# early-bird.net
KiCad netlist of a schematic drawn in EAGLE
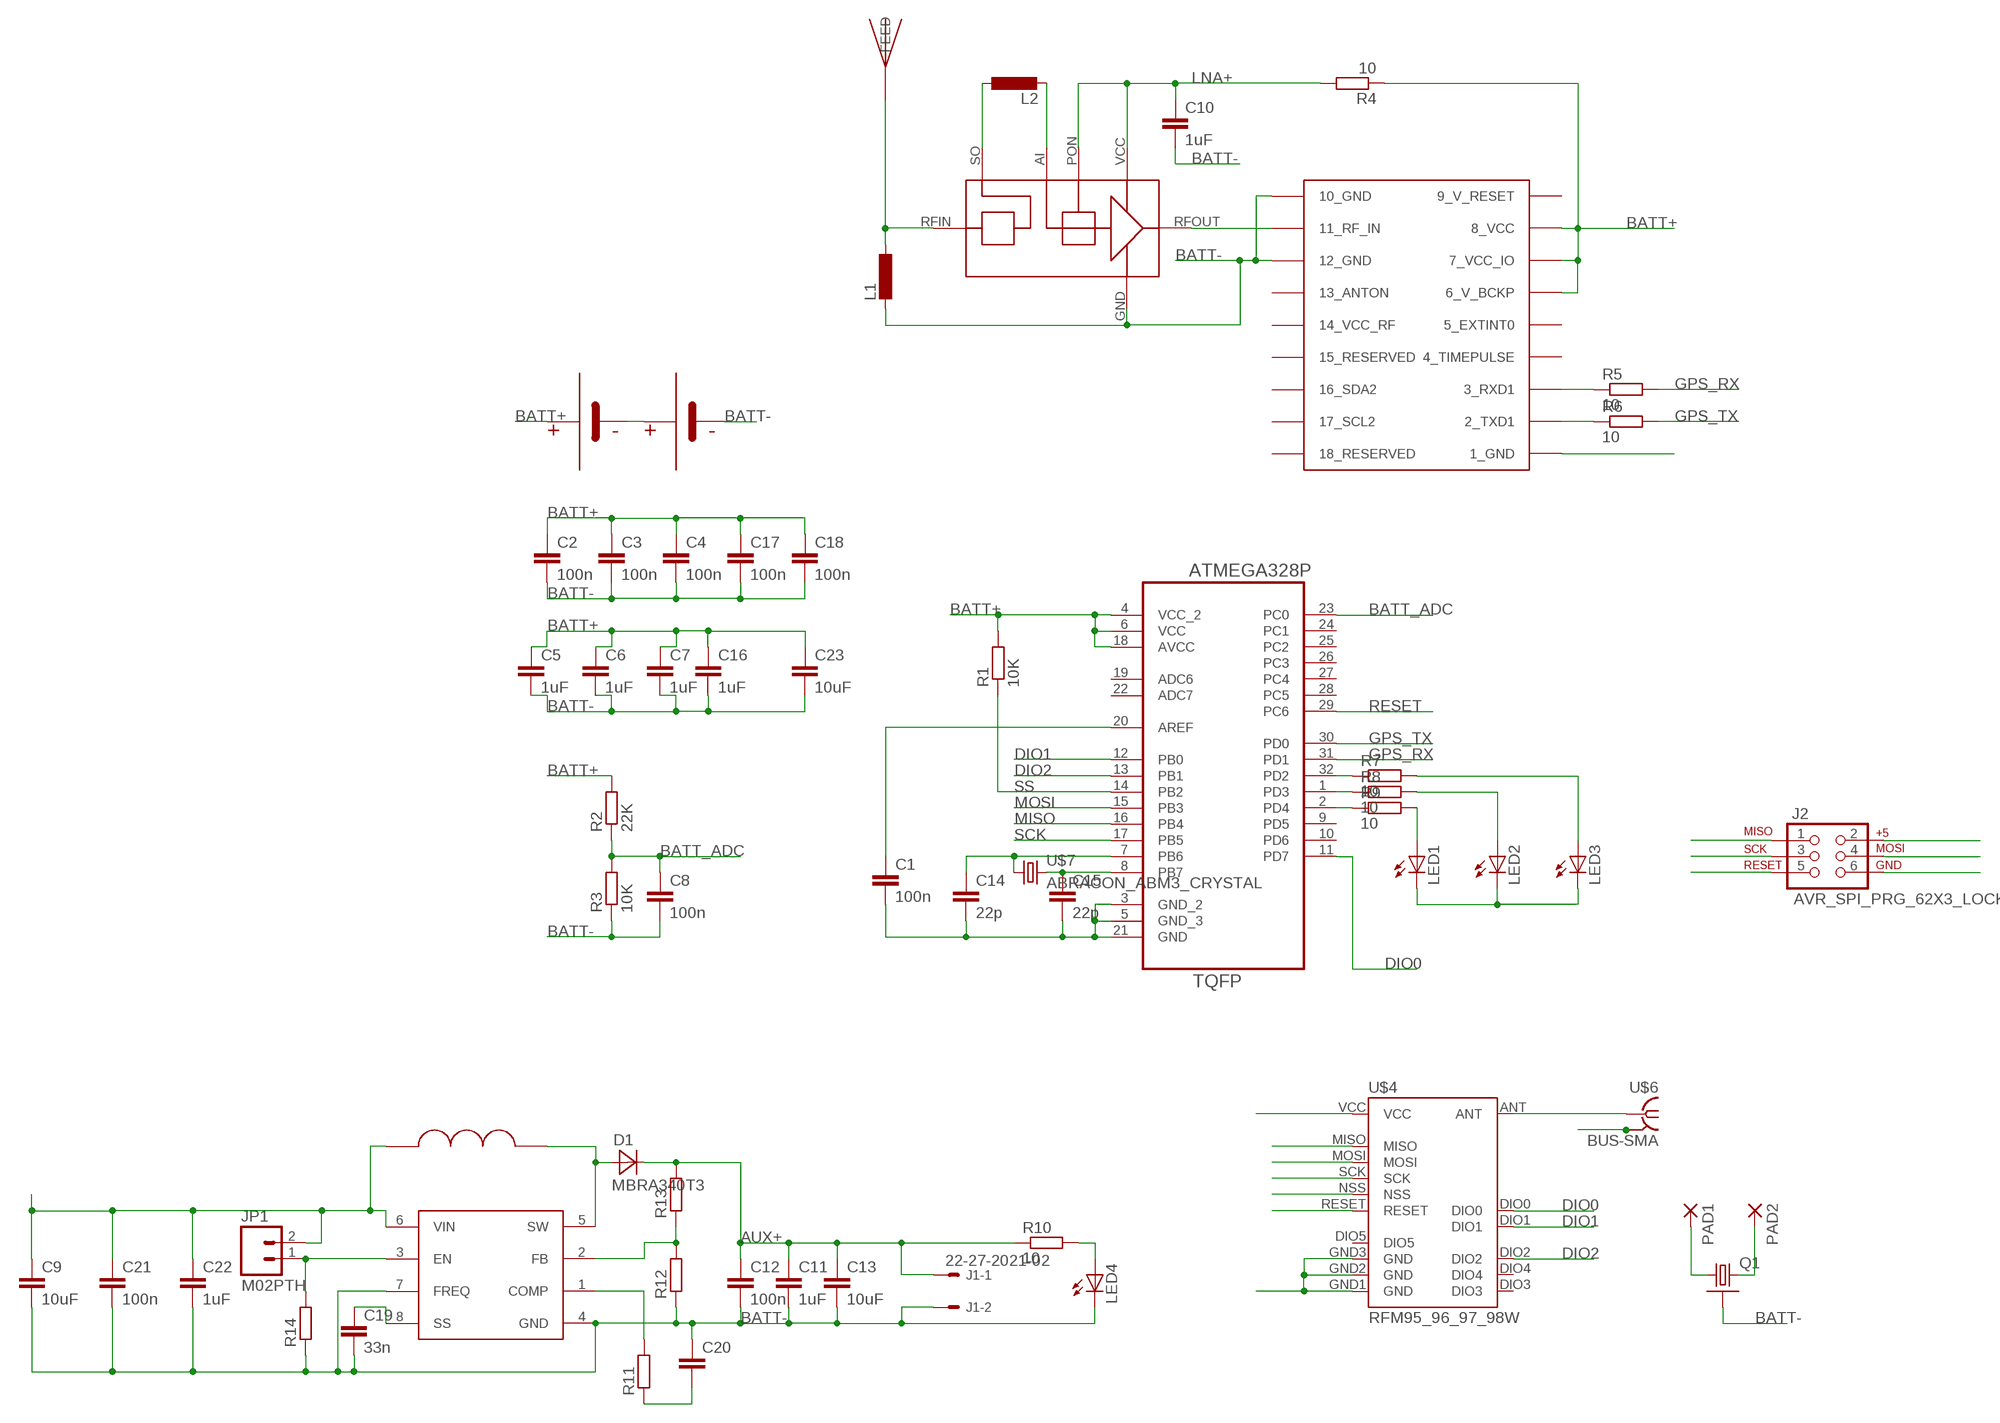
[diagram p0: schematic, sheet 1]

(export (version "E")
  (design (tool "Eeschema 10.0.6"))
  (components
    (comp (ref "C1")
      (value "100n")
      (footprint "eagle-import:C0402")
      (libsource (lib "eagle-import") (part "C-EUC0402"))
    )
    (comp (ref "C2")
      (value "100n")
      (footprint "eagle-import:C0402")
      (libsource (lib "eagle-import") (part "C-EUC0402"))
    )
    (comp (ref "C3")
      (value "100n")
      (footprint "eagle-import:C0402")
      (libsource (lib "eagle-import") (part "C-EUC0402"))
    )
    (comp (ref "C4")
      (value "100n")
      (footprint "eagle-import:C0402")
      (libsource (lib "eagle-import") (part "C-EUC0402"))
    )
    (comp (ref "C5")
      (value "1uF")
      (footprint "eagle-import:C0603")
      (libsource (lib "eagle-import") (part "C-EUC0603"))
    )
    (comp (ref "C6")
      (value "1uF")
      (footprint "eagle-import:C0603")
      (libsource (lib "eagle-import") (part "C-EUC0603"))
    )
    (comp (ref "C7")
      (value "1uF")
      (footprint "eagle-import:C0603")
      (libsource (lib "eagle-import") (part "C-EUC0603"))
    )
    (comp (ref "C8")
      (value "100n")
      (footprint "eagle-import:C0402")
      (libsource (lib "eagle-import") (part "C-EUC0402"))
    )
    (comp (ref "C9")
      (value "10uF")
      (footprint "eagle-import:C1210")
      (libsource (lib "eagle-import") (part "C-EUC1210"))
    )
    (comp (ref "C10")
      (value "1uF")
      (footprint "eagle-import:C0603")
      (libsource (lib "eagle-import") (part "C-EUC0603"))
    )
    (comp (ref "C11")
      (value "1uF")
      (footprint "eagle-import:C0603")
      (libsource (lib "eagle-import") (part "C-EUC0603"))
    )
    (comp (ref "C12")
      (value "100n")
      (footprint "eagle-import:C0402")
      (libsource (lib "eagle-import") (part "C-EUC0402"))
    )
    (comp (ref "C13")
      (value "10uF")
      (footprint "eagle-import:C1210")
      (libsource (lib "eagle-import") (part "C-EUC1210"))
    )
    (comp (ref "C14")
      (value "22p")
      (footprint "eagle-import:C0402")
      (libsource (lib "eagle-import") (part "C-EUC0402"))
    )
    (comp (ref "C15")
      (value "22p")
      (footprint "eagle-import:C0402")
      (libsource (lib "eagle-import") (part "C-EUC0402"))
    )
    (comp (ref "C16")
      (value "1uF")
      (footprint "eagle-import:C0603")
      (libsource (lib "eagle-import") (part "C-EUC0603"))
    )
    (comp (ref "C17")
      (value "100n")
      (footprint "eagle-import:C0402")
      (libsource (lib "eagle-import") (part "C-EUC0402"))
    )
    (comp (ref "C18")
      (value "100n")
      (footprint "eagle-import:C0402")
      (libsource (lib "eagle-import") (part "C-EUC0402"))
    )
    (comp (ref "C19")
      (value "33n")
      (footprint "eagle-import:C0402")
      (libsource (lib "eagle-import") (part "C-EUC0402"))
    )
    (comp (ref "C20")
      (value "C-EUC0402")
      (footprint "eagle-import:C0402")
      (libsource (lib "eagle-import") (part "C-EUC0402"))
    )
    (comp (ref "C21")
      (value "100n")
      (footprint "eagle-import:C0402")
      (libsource (lib "eagle-import") (part "C-EUC0402"))
    )
    (comp (ref "C22")
      (value "1uF")
      (footprint "eagle-import:C0603")
      (libsource (lib "eagle-import") (part "C-EUC0603"))
    )
    (comp (ref "C23")
      (value "10uF")
      (footprint "eagle-import:C1210")
      (libsource (lib "eagle-import") (part "C-EUC1210"))
    )
    (comp (ref "D1")
      (value "MBRA340T3")
      (footprint "eagle-import:SMA")
      (libsource (lib "eagle-import") (part "MBRA340T3"))
    )
    (comp (ref "J1")
      (value "22-27-2021-02")
      (footprint "eagle-import:6410-02")
      (libsource (lib "eagle-import") (part "22-?-0227-2021"))
    )
    (comp (ref "J2")
      (value "AVR_SPI_PRG_62X3_LOCK")
      (footprint "eagle-import:2X3_LOCK")
      (libsource (lib "eagle-import") (part "AVR_SPI_PRG_62X3_LOCK"))
    )
    (comp (ref "JP1")
      (value "M02PTH")
      (footprint "eagle-import:1X02")
      (libsource (lib "eagle-import") (part "M02PTH"))
    )
    (comp (ref "L1")
      (value "L-EUL2012C")
      (footprint "eagle-import:L2012C")
      (libsource (lib "eagle-import") (part "L-EUL2012C"))
    )
    (comp (ref "L2")
      (value "L-EUL2012C")
      (footprint "eagle-import:L2012C")
      (libsource (lib "eagle-import") (part "L-EUL2012C"))
    )
    (comp (ref "LED1")
      (value "LEDCHIPLED_1206")
      (footprint "eagle-import:CHIPLED_1206")
      (libsource (lib "eagle-import") (part "LEDCHIPLED_1206"))
    )
    (comp (ref "LED2")
      (value "LEDCHIPLED_1206")
      (footprint "eagle-import:CHIPLED_1206")
      (libsource (lib "eagle-import") (part "LEDCHIPLED_1206"))
    )
    (comp (ref "LED3")
      (value "LEDCHIPLED_1206")
      (footprint "eagle-import:CHIPLED_1206")
      (libsource (lib "eagle-import") (part "LEDCHIPLED_1206"))
    )
    (comp (ref "LED4")
      (value "LEDCHIPLED_1206")
      (footprint "eagle-import:CHIPLED_1206")
      (libsource (lib "eagle-import") (part "LEDCHIPLED_1206"))
    )
    (comp (ref "PAD1")
      (value "SMD2")
      (footprint "eagle-import:SMD1,27-2,54")
      (libsource (lib "eagle-import") (part "SMD2"))
    )
    (comp (ref "PAD2")
      (value "SMD2")
      (footprint "eagle-import:SMD1,27-2,54")
      (libsource (lib "eagle-import") (part "SMD2"))
    )
    (comp (ref "Q1")
      (value "CRYSTALCTS406")
      (footprint "eagle-import:CTS406")
      (libsource (lib "eagle-import") (part "CRYSTALCTS406"))
    )
    (comp (ref "R1")
      (value "10K")
      (footprint "eagle-import:R0402")
      (libsource (lib "eagle-import") (part "R-EU_R0402"))
    )
    (comp (ref "R2")
      (value "22K")
      (footprint "eagle-import:R0402")
      (libsource (lib "eagle-import") (part "R-EU_R0402"))
    )
    (comp (ref "R3")
      (value "10K")
      (footprint "eagle-import:R0402")
      (libsource (lib "eagle-import") (part "R-EU_R0402"))
    )
    (comp (ref "R4")
      (value "10")
      (footprint "eagle-import:R0402")
      (libsource (lib "eagle-import") (part "R-EU_R0402"))
    )
    (comp (ref "R5")
      (value "10")
      (footprint "eagle-import:R0402")
      (libsource (lib "eagle-import") (part "R-EU_R0402"))
    )
    (comp (ref "R6")
      (value "10")
      (footprint "eagle-import:R0402")
      (libsource (lib "eagle-import") (part "R-EU_R0402"))
    )
    (comp (ref "R7")
      (value "10")
      (footprint "eagle-import:R0402")
      (libsource (lib "eagle-import") (part "R-EU_R0402"))
    )
    (comp (ref "R8")
      (value "10")
      (footprint "eagle-import:R0402")
      (libsource (lib "eagle-import") (part "R-EU_R0402"))
    )
    (comp (ref "R9")
      (value "10")
      (footprint "eagle-import:R0402")
      (libsource (lib "eagle-import") (part "R-EU_R0402"))
    )
    (comp (ref "R10")
      (value "10")
      (footprint "eagle-import:R0402")
      (libsource (lib "eagle-import") (part "R-EU_R0402"))
    )
    (comp (ref "R11")
      (value "R-EU_R0402")
      (footprint "eagle-import:R0402")
      (libsource (lib "eagle-import") (part "R-EU_R0402"))
    )
    (comp (ref "R12")
      (value "R-EU_R0402")
      (footprint "eagle-import:R0402")
      (libsource (lib "eagle-import") (part "R-EU_R0402"))
    )
    (comp (ref "R13")
      (value "R-EU_R0402")
      (footprint "eagle-import:R0402")
      (libsource (lib "eagle-import") (part "R-EU_R0402"))
    )
    (comp (ref "R14")
      (value "R-EU_R0402")
      (footprint "eagle-import:R0402")
      (libsource (lib "eagle-import") (part "R-EU_R0402"))
    )
    (comp (ref "U$1")
      (value "KEYSTONE-92-AA-BATTERY-HOLDER")
      (footprint "eagle-import:KEYSTONE-92-AA-BATTERY")
      (libsource (lib "eagle-import") (part "KEYSTONE-92-AA-BATTERY-HOLDER"))
    )
    (comp (ref "U$2")
      (value "KEYSTONE-92-AA-BATTERY-HOLDER")
      (footprint "eagle-import:KEYSTONE-92-AA-BATTERY")
      (libsource (lib "eagle-import") (part "KEYSTONE-92-AA-BATTERY-HOLDER"))
    )
    (comp (ref "U$3")
      (value "JTI_ANTENNA-1575AT43A40")
      (footprint "eagle-import:JTI_ANTENNA-1575AT43A40")
      (libsource (lib "eagle-import") (part "JTI_ANTENNA-1575AT43A40"))
    )
    (comp (ref "U$4")
      (value "RFM95_96_97_98W")
      (footprint "eagle-import:RFM95_96_97_98W")
      (libsource (lib "eagle-import") (part "RFM95_96_97_98W"))
    )
    (comp (ref "U$5")
      (value "UBLOX_MAX")
      (footprint "eagle-import:UBLOX_MAX")
      (libsource (lib "eagle-import") (part "UBLOX_MAX"))
    )
    (comp (ref "U$6")
      (value "BUS-SMA")
      (footprint "eagle-import:BUS-SMA")
      (libsource (lib "eagle-import") (part "BUS-SMA"))
    )
    (comp (ref "U$7")
      (value "ABRACON_ABM3_CRYSTAL")
      (footprint "eagle-import:ABRACON_ABM3_CRYSTAL")
      (libsource (lib "eagle-import") (part "ABRACON_ABM3_CRYSTAL"))
    )
    (comp (ref "U$8")
      (value "ADP1612")
      (footprint "eagle-import:SOP65P490X110-8N")
      (libsource (lib "eagle-import") (part "ADP1612"))
    )
    (comp (ref "U$9")
      (value "BGM1034N7")
      (footprint "eagle-import:TSNP-7-10")
      (libsource (lib "eagle-import") (part "BGM1034N7"))
    )
    (comp (ref "U$10")
      (value "MULTICOMP_8MM_INDUCTOR")
      (footprint "eagle-import:8MM_SQ_INDUCTOR")
      (libsource (lib "eagle-import") (part "MULTICOMP_8MM_INDUCTOR"))
    )
    (comp (ref "U1")
      (value "ATMEGA328P-AU")
      (footprint "eagle-import:QFP80P900X900X120-32N")
      (libsource (lib "eagle-import") (part "ATMEGA328P-AU"))
    )
  )
  (nets
    (net (code "1") (name "/9_V_RESET") (class "Default")
      (node (ref "U$5") (pin "9_V_RESET") (pinfunction "9_V_RESET_9_V_RESET") (pintype "power_in"))
    )
    (net (code "2") (name "/AUX+") (class "Default")
      (node (ref "C11") (pin "1") (pinfunction "1_1") (pintype "passive"))
      (node (ref "C12") (pin "1") (pinfunction "1_1") (pintype "passive"))
      (node (ref "C13") (pin "1") (pinfunction "1_1") (pintype "passive"))
      (node (ref "D1") (pin "C") (pinfunction "C_C") (pintype "passive"))
      (node (ref "J1") (pin "1") (pinfunction "S_1") (pintype "passive"))
      (node (ref "R10") (pin "1") (pinfunction "1_1") (pintype "passive"))
      (node (ref "R13") (pin "2") (pinfunction "2_2") (pintype "passive"))
    )
    (net (code "3") (name "/BATT+") (class "Default")
      (node (ref "C16") (pin "1") (pinfunction "1_1") (pintype "passive"))
      (node (ref "C17") (pin "1") (pinfunction "1_1") (pintype "passive"))
      (node (ref "C18") (pin "1") (pinfunction "1_1") (pintype "passive"))
      (node (ref "C2") (pin "1") (pinfunction "1_1") (pintype "passive"))
      (node (ref "C21") (pin "1") (pinfunction "1_1") (pintype "passive"))
      (node (ref "C22") (pin "1") (pinfunction "1_1") (pintype "passive"))
      (node (ref "C23") (pin "1") (pinfunction "1_1") (pintype "passive"))
      (node (ref "C3") (pin "1") (pinfunction "1_1") (pintype "passive"))
      (node (ref "C4") (pin "1") (pinfunction "1_1") (pintype "passive"))
      (node (ref "C5") (pin "1") (pinfunction "1_1") (pintype "passive"))
      (node (ref "C6") (pin "1") (pinfunction "1_1") (pintype "passive"))
      (node (ref "C7") (pin "1") (pinfunction "1_1") (pintype "passive"))
      (node (ref "C9") (pin "1") (pinfunction "1_1") (pintype "passive"))
      (node (ref "J2") (pin "2") (pinfunction "2_2") (pintype "passive"))
      (node (ref "JP1") (pin "2") (pinfunction "2_2") (pintype "passive"))
      (node (ref "R1") (pin "2") (pinfunction "2_2") (pintype "passive"))
      (node (ref "R2") (pin "2") (pinfunction "2_2") (pintype "passive"))
      (node (ref "R4") (pin "1") (pinfunction "1_1") (pintype "passive"))
      (node (ref "U$1") (pin "VBATT") (pinfunction "BATT+_VBATT") (pintype "bidirectional"))
      (node (ref "U$1") (pin "VBATT1") (pinfunction "BATT+_VBATT1") (pintype "bidirectional"))
      (node (ref "U$10") (pin "P$2") (pinfunction "P$2_P$2") (pintype "bidirectional"))
      (node (ref "U$4") (pin "VCC") (pinfunction "VCC_VCC") (pintype "bidirectional"))
      (node (ref "U$5") (pin "6_V_BCKP") (pinfunction "6_V_BCKP_6_V_BCKP") (pintype "bidirectional"))
      (node (ref "U$5") (pin "7_VCC_IO") (pinfunction "7_VCC_IO_7_VCC_IO") (pintype "power_in"))
      (node (ref "U$5") (pin "8_VCC") (pinfunction "8_VCC_8_VCC") (pintype "power_in"))
      (node (ref "U$8") (pin "6") (pinfunction "VIN_6") (pintype "bidirectional"))
      (node (ref "U1") (pin "18") (pinfunction "AVCC_18") (pintype "power_in"))
      (node (ref "U1") (pin "4") (pinfunction "VCC_2_4") (pintype "power_in"))
      (node (ref "U1") (pin "6") (pinfunction "VCC_6") (pintype "power_in"))
    )
    (net (code "4") (name "/BATT-") (class "Default")
      (node (ref "C1") (pin "2") (pinfunction "2_2") (pintype "passive"))
      (node (ref "C10") (pin "2") (pinfunction "2_2") (pintype "passive"))
      (node (ref "C11") (pin "2") (pinfunction "2_2") (pintype "passive"))
      (node (ref "C12") (pin "2") (pinfunction "2_2") (pintype "passive"))
      (node (ref "C13") (pin "2") (pinfunction "2_2") (pintype "passive"))
      (node (ref "C14") (pin "2") (pinfunction "2_2") (pintype "passive"))
      (node (ref "C15") (pin "2") (pinfunction "2_2") (pintype "passive"))
      (node (ref "C16") (pin "2") (pinfunction "2_2") (pintype "passive"))
      (node (ref "C17") (pin "2") (pinfunction "2_2") (pintype "passive"))
      (node (ref "C18") (pin "2") (pinfunction "2_2") (pintype "passive"))
      (node (ref "C19") (pin "2") (pinfunction "2_2") (pintype "passive"))
      (node (ref "C2") (pin "2") (pinfunction "2_2") (pintype "passive"))
      (node (ref "C20") (pin "1") (pinfunction "1_1") (pintype "passive"))
      (node (ref "C21") (pin "2") (pinfunction "2_2") (pintype "passive"))
      (node (ref "C22") (pin "2") (pinfunction "2_2") (pintype "passive"))
      (node (ref "C23") (pin "2") (pinfunction "2_2") (pintype "passive"))
      (node (ref "C3") (pin "2") (pinfunction "2_2") (pintype "passive"))
      (node (ref "C4") (pin "2") (pinfunction "2_2") (pintype "passive"))
      (node (ref "C5") (pin "2") (pinfunction "2_2") (pintype "passive"))
      (node (ref "C6") (pin "2") (pinfunction "2_2") (pintype "passive"))
      (node (ref "C7") (pin "2") (pinfunction "2_2") (pintype "passive"))
      (node (ref "C8") (pin "2") (pinfunction "2_2") (pintype "passive"))
      (node (ref "C9") (pin "2") (pinfunction "2_2") (pintype "passive"))
      (node (ref "J1") (pin "2") (pinfunction "S_2") (pintype "passive"))
      (node (ref "J2") (pin "6") (pinfunction "6_6") (pintype "passive"))
      (node (ref "L1") (pin "2") (pinfunction "2_2") (pintype "passive"))
      (node (ref "LED1") (pin "C") (pinfunction "C_C") (pintype "passive"))
      (node (ref "LED2") (pin "C") (pinfunction "C_C") (pintype "passive"))
      (node (ref "LED3") (pin "C") (pinfunction "C_C") (pintype "passive"))
      (node (ref "LED4") (pin "C") (pinfunction "C_C") (pintype "passive"))
      (node (ref "Q1") (pin "2") (pinfunction "P$1_2") (pintype "bidirectional"))
      (node (ref "Q1") (pin "4") (pinfunction "P$1_4") (pintype "bidirectional"))
      (node (ref "R12") (pin "1") (pinfunction "1_1") (pintype "passive"))
      (node (ref "R14") (pin "1") (pinfunction "1_1") (pintype "passive"))
      (node (ref "R3") (pin "1") (pinfunction "1_1") (pintype "passive"))
      (node (ref "U$2") (pin "GND") (pinfunction "BATT-_GND") (pintype "bidirectional"))
      (node (ref "U$2") (pin "GND2") (pinfunction "BATT-_GND2") (pintype "bidirectional"))
      (node (ref "U$4") (pin "GND1") (pinfunction "GND_GND1") (pintype "power_in"))
      (node (ref "U$4") (pin "GND2") (pinfunction "GND_GND2") (pintype "power_in"))
      (node (ref "U$4") (pin "GND3") (pinfunction "GND_GND3") (pintype "power_in"))
      (node (ref "U$5") (pin "10_GND") (pinfunction "10_GND_10_GND") (pintype "power_in"))
      (node (ref "U$5") (pin "12_GND") (pinfunction "12_GND_12_GND") (pintype "power_in"))
      (node (ref "U$5") (pin "1_GND") (pinfunction "1_GND_1_GND") (pintype "power_in"))
      (node (ref "U$6") (pin "2") (pinfunction "GND_2") (pintype "power_in"))
      (node (ref "U$6") (pin "3") (pinfunction "GND_3") (pintype "power_in"))
      (node (ref "U$6") (pin "4") (pinfunction "GND_4") (pintype "power_in"))
      (node (ref "U$6") (pin "5") (pinfunction "GND_5") (pintype "power_in"))
      (node (ref "U$8") (pin "4") (pinfunction "GND_4") (pintype "bidirectional"))
      (node (ref "U$8") (pin "7") (pinfunction "FREQ_7") (pintype "bidirectional"))
      (node (ref "U$9") (pin "GND") (pinfunction "GND_GND") (pintype "bidirectional"))
      (node (ref "U1") (pin "21") (pinfunction "GND_21") (pintype "passive"))
      (node (ref "U1") (pin "3") (pinfunction "GND_2_3") (pintype "passive"))
      (node (ref "U1") (pin "5") (pinfunction "GND_3_5") (pintype "passive"))
    )
    (net (code "5") (name "/BATT_ADC") (class "Default")
      (node (ref "C8") (pin "1") (pinfunction "1_1") (pintype "passive"))
      (node (ref "R2") (pin "1") (pinfunction "1_1") (pintype "passive"))
      (node (ref "R3") (pin "2") (pinfunction "2_2") (pintype "passive"))
      (node (ref "U1") (pin "23") (pinfunction "PC0_23") (pintype "bidirectional"))
    )
    (net (code "6") (name "/DIO0") (class "Default")
      (node (ref "U$4") (pin "DIO0") (pinfunction "DIO0_DIO0") (pintype "input"))
      (node (ref "U1") (pin "11") (pinfunction "PD7_11") (pintype "bidirectional"))
    )
    (net (code "7") (name "/DIO1") (class "Default")
      (node (ref "U$4") (pin "DIO1") (pinfunction "DIO1_DIO1") (pintype "input"))
      (node (ref "U1") (pin "12") (pinfunction "PB0_12") (pintype "bidirectional"))
    )
    (net (code "8") (name "/DIO2") (class "Default")
      (node (ref "U$4") (pin "DIO2") (pinfunction "DIO2_DIO2") (pintype "bidirectional"))
      (node (ref "U1") (pin "13") (pinfunction "PB1_13") (pintype "bidirectional"))
    )
    (net (code "9") (name "/GPS_RX") (class "Default")
      (node (ref "R5") (pin "2") (pinfunction "2_2") (pintype "passive"))
      (node (ref "U1") (pin "31") (pinfunction "PD1_31") (pintype "bidirectional"))
    )
    (net (code "10") (name "/GPS_TX") (class "Default")
      (node (ref "R6") (pin "2") (pinfunction "2_2") (pintype "passive"))
      (node (ref "U1") (pin "30") (pinfunction "PD0_30") (pintype "bidirectional"))
    )
    (net (code "11") (name "/LNA+") (class "Default")
      (node (ref "C10") (pin "1") (pinfunction "1_1") (pintype "passive"))
      (node (ref "R4") (pin "2") (pinfunction "2_2") (pintype "passive"))
      (node (ref "U$9") (pin "PON") (pinfunction "PON_PON") (pintype "bidirectional"))
      (node (ref "U$9") (pin "VCC") (pinfunction "VCC_VCC") (pintype "bidirectional"))
    )
    (net (code "12") (name "/MISO") (class "Default")
      (node (ref "J2") (pin "1") (pinfunction "1_1") (pintype "passive"))
      (node (ref "U$4") (pin "MISO") (pinfunction "MISO_MISO") (pintype "output"))
      (node (ref "U1") (pin "16") (pinfunction "PB4_16") (pintype "bidirectional"))
    )
    (net (code "13") (name "/MOSI") (class "Default")
      (node (ref "J2") (pin "4") (pinfunction "4_4") (pintype "passive"))
      (node (ref "U$4") (pin "MOSI") (pinfunction "MOSI_MOSI") (pintype "input"))
      (node (ref "U1") (pin "15") (pinfunction "PB3_15") (pintype "bidirectional"))
    )
    (net (code "14") (name "/RESET") (class "Default")
      (node (ref "J2") (pin "5") (pinfunction "5_5") (pintype "passive"))
      (node (ref "U1") (pin "29") (pinfunction "PC6_29") (pintype "bidirectional"))
    )
    (net (code "15") (name "/SCK") (class "Default")
      (node (ref "J2") (pin "3") (pinfunction "3_3") (pintype "passive"))
      (node (ref "U$4") (pin "SCK") (pinfunction "SCK_SCK") (pintype "input"))
      (node (ref "U1") (pin "17") (pinfunction "PB5_17") (pintype "bidirectional"))
    )
    (net (code "16") (name "/SS") (class "Default")
      (node (ref "R1") (pin "1") (pinfunction "1_1") (pintype "passive"))
      (node (ref "U$4") (pin "NSS") (pinfunction "NSS_NSS") (pintype "input"))
      (node (ref "U1") (pin "14") (pinfunction "PB2_14") (pintype "bidirectional"))
    )
    (net (code "17") (name "Net-(C20-Pad2)") (class "Default")
      (node (ref "C20") (pin "2") (pinfunction "2_2") (pintype "passive"))
      (node (ref "R11") (pin "1") (pinfunction "1_1") (pintype "passive"))
    )
    (net (code "18") (name "Net-(L1-Pad1)") (class "Default")
      (node (ref "L1") (pin "1") (pinfunction "1_1") (pintype "passive"))
      (node (ref "U$3") (pin "FEED") (pinfunction "FEED_FEED") (pintype "bidirectional"))
      (node (ref "U$9") (pin "RFIN") (pinfunction "RFIN_RFIN") (pintype "bidirectional"))
    )
    (net (code "19") (name "Net-(L2-Pad1)") (class "Default")
      (node (ref "L2") (pin "1") (pinfunction "1_1") (pintype "passive"))
      (node (ref "U$9") (pin "SO") (pinfunction "SO_SO") (pintype "bidirectional"))
    )
    (net (code "20") (name "Net-(L2-Pad2)") (class "Default")
      (node (ref "L2") (pin "2") (pinfunction "2_2") (pintype "passive"))
      (node (ref "U$9") (pin "AI") (pinfunction "AI_AI") (pintype "bidirectional"))
    )
    (net (code "21") (name "Net-(LED1-PadA)") (class "Default")
      (node (ref "LED1") (pin "A") (pinfunction "A_A") (pintype "passive"))
      (node (ref "R9") (pin "2") (pinfunction "2_2") (pintype "passive"))
    )
    (net (code "22") (name "Net-(LED2-PadA)") (class "Default")
      (node (ref "LED2") (pin "A") (pinfunction "A_A") (pintype "passive"))
      (node (ref "R8") (pin "2") (pinfunction "2_2") (pintype "passive"))
    )
    (net (code "23") (name "Net-(LED3-PadA)") (class "Default")
      (node (ref "LED3") (pin "A") (pinfunction "A_A") (pintype "passive"))
      (node (ref "R7") (pin "2") (pinfunction "2_2") (pintype "passive"))
    )
    (net (code "24") (name "Net-(LED4-PadA)") (class "Default")
      (node (ref "LED4") (pin "A") (pinfunction "A_A") (pintype "passive"))
      (node (ref "R10") (pin "2") (pinfunction "2_2") (pintype "passive"))
    )
    (net (code "25") (name "Net-(PAD1-P)") (class "Default")
      (node (ref "PAD1") (pin "1") (pinfunction "P_1") (pintype "passive"))
      (node (ref "Q1") (pin "1") (pinfunction "1_1") (pintype "passive"))
    )
    (net (code "26") (name "Net-(PAD2-P)") (class "Default")
      (node (ref "PAD2") (pin "1") (pinfunction "P_1") (pintype "passive"))
      (node (ref "Q1") (pin "3") (pinfunction "2_3") (pintype "passive"))
    )
    (net (code "27") (name "Net-(R5-Pad1)") (class "Default")
      (node (ref "R5") (pin "1") (pinfunction "1_1") (pintype "passive"))
      (node (ref "U$5") (pin "3_RXD1") (pinfunction "3_RXD1_3_RXD1") (pintype "bidirectional"))
    )
    (net (code "28") (name "Net-(R6-Pad1)") (class "Default")
      (node (ref "R6") (pin "1") (pinfunction "1_1") (pintype "passive"))
      (node (ref "U$5") (pin "2_TXD1") (pinfunction "2_TXD1_2_TXD1") (pintype "bidirectional"))
    )
    (net (code "29") (name "Net-(U$1-BATT--PadGND)") (class "Default")
      (node (ref "U$1") (pin "GND") (pinfunction "BATT-_GND") (pintype "bidirectional"))
      (node (ref "U$1") (pin "GND2") (pinfunction "BATT-_GND2") (pintype "bidirectional"))
      (node (ref "U$2") (pin "VBATT") (pinfunction "BATT+_VBATT") (pintype "bidirectional"))
      (node (ref "U$2") (pin "VBATT1") (pinfunction "BATT+_VBATT1") (pintype "bidirectional"))
    )
    (net (code "30") (name "Net-(U$4-PadANT)") (class "Default")
      (node (ref "U$4") (pin "ANT") (pinfunction "ANT_ANT") (pintype "bidirectional"))
      (node (ref "U$6") (pin "1") (pinfunction "1_1") (pintype "passive"))
    )
    (net (code "31") (name "Net-(U$5-Pad11_RF_IN)") (class "Default")
      (node (ref "U$5") (pin "11_RF_IN") (pinfunction "11_RF_IN_11_RF_IN") (pintype "bidirectional"))
      (node (ref "U$9") (pin "RFOUT") (pinfunction "RFOUT_RFOUT") (pintype "bidirectional"))
    )
    (net (code "32") (name "Net-(U$7-1)") (class "Default")
      (node (ref "C14") (pin "1") (pinfunction "1_1") (pintype "passive"))
      (node (ref "U$7") (pin "P$1") (pinfunction "1_P$1") (pintype "passive"))
      (node (ref "U1") (pin "7") (pinfunction "PB6_7") (pintype "bidirectional"))
    )
    (net (code "33") (name "Net-(U$7-2)") (class "Default")
      (node (ref "C15") (pin "1") (pinfunction "1_1") (pintype "passive"))
      (node (ref "U$7") (pin "P$2") (pinfunction "2_P$2") (pintype "passive"))
      (node (ref "U1") (pin "8") (pinfunction "PB7_8") (pintype "bidirectional"))
    )
    (net (code "34") (name "Net-(U$8-COMP)") (class "Default")
      (node (ref "R11") (pin "2") (pinfunction "2_2") (pintype "passive"))
      (node (ref "U$8") (pin "1") (pinfunction "COMP_1") (pintype "bidirectional"))
    )
    (net (code "35") (name "Net-(U$8-EN)") (class "Default")
      (node (ref "JP1") (pin "1") (pinfunction "1_1") (pintype "passive"))
      (node (ref "R14") (pin "2") (pinfunction "2_2") (pintype "passive"))
      (node (ref "U$8") (pin "3") (pinfunction "EN_3") (pintype "bidirectional"))
    )
    (net (code "36") (name "Net-(U$8-FB)") (class "Default")
      (node (ref "R12") (pin "2") (pinfunction "2_2") (pintype "passive"))
      (node (ref "R13") (pin "1") (pinfunction "1_1") (pintype "passive"))
      (node (ref "U$8") (pin "2") (pinfunction "FB_2") (pintype "bidirectional"))
    )
    (net (code "37") (name "Net-(U$8-SS)") (class "Default")
      (node (ref "C19") (pin "1") (pinfunction "1_1") (pintype "passive"))
      (node (ref "U$8") (pin "8") (pinfunction "SS_8") (pintype "bidirectional"))
    )
    (net (code "38") (name "Net-(U$8-SW)") (class "Default")
      (node (ref "D1") (pin "A") (pinfunction "A_A") (pintype "passive"))
      (node (ref "U$10") (pin "P$1") (pinfunction "P$1_P$1") (pintype "bidirectional"))
      (node (ref "U$8") (pin "5") (pinfunction "SW_5") (pintype "bidirectional"))
    )
    (net (code "39") (name "Net-(U1-AREF)") (class "Default")
      (node (ref "C1") (pin "1") (pinfunction "1_1") (pintype "passive"))
      (node (ref "U1") (pin "20") (pinfunction "AREF_20") (pintype "input"))
    )
    (net (code "40") (name "Net-(U1-PD2)") (class "Default")
      (node (ref "R7") (pin "1") (pinfunction "1_1") (pintype "passive"))
      (node (ref "U1") (pin "32") (pinfunction "PD2_32") (pintype "bidirectional"))
    )
    (net (code "41") (name "Net-(U1-PD3)") (class "Default")
      (node (ref "R8") (pin "1") (pinfunction "1_1") (pintype "passive"))
      (node (ref "U1") (pin "1") (pinfunction "PD3_1") (pintype "bidirectional"))
    )
    (net (code "42") (name "Net-(U1-PD4)") (class "Default")
      (node (ref "R9") (pin "1") (pinfunction "1_1") (pintype "passive"))
      (node (ref "U1") (pin "2") (pinfunction "PD4_2") (pintype "bidirectional"))
    )
    (net (code "43") (name "unconnected-(U$4-PadDIO3)") (class "Default")
      (node (ref "U$4") (pin "DIO3") (pinfunction "DIO3_DIO3") (pintype "bidirectional"))
    )
    (net (code "44") (name "unconnected-(U$4-PadDIO4)") (class "Default")
      (node (ref "U$4") (pin "DIO4") (pinfunction "DIO4_DIO4") (pintype "bidirectional"))
    )
    (net (code "45") (name "unconnected-(U$4-PadDIO5)") (class "Default")
      (node (ref "U$4") (pin "DIO5") (pinfunction "DIO5_DIO5") (pintype "input"))
    )
    (net (code "46") (name "unconnected-(U$4-PadRESET)") (class "Default")
      (node (ref "U$4") (pin "RESET") (pinfunction "RESET_RESET") (pintype "output"))
    )
    (net (code "47") (name "unconnected-(U$5-Pad4_TIMEPULSE)") (class "Default")
      (node (ref "U$5") (pin "4_TIMEPULSE") (pinfunction "4_TIMEPULSE_4_TIMEPULSE") (pintype "bidirectional"))
    )
    (net (code "48") (name "unconnected-(U$5-Pad5_EXTINT0)") (class "Default")
      (node (ref "U$5") (pin "5_EXTINT0") (pinfunction "5_EXTINT0_5_EXTINT0") (pintype "bidirectional"))
    )
    (net (code "49") (name "unconnected-(U$5-Pad13_ANTON)") (class "Default")
      (node (ref "U$5") (pin "13_ANTON") (pinfunction "13_ANTON_13_ANTON") (pintype "bidirectional"))
    )
    (net (code "50") (name "unconnected-(U$5-Pad14_VCC_RF)") (class "Default")
      (node (ref "U$5") (pin "14_VCC_RF") (pinfunction "14_VCC_RF_14_VCC_RF") (pintype "bidirectional"))
    )
    (net (code "51") (name "unconnected-(U$5-Pad15_RESERVED)") (class "Default")
      (node (ref "U$5") (pin "15_RESERVED") (pinfunction "15_RESERVED_15_RESERVED") (pintype "bidirectional"))
    )
    (net (code "52") (name "unconnected-(U$5-Pad16_SDA2)") (class "Default")
      (node (ref "U$5") (pin "16_SDA2") (pinfunction "16_SDA2_16_SDA2") (pintype "bidirectional"))
    )
    (net (code "53") (name "unconnected-(U$5-Pad17_SCL2)") (class "Default")
      (node (ref "U$5") (pin "17_SCL2") (pinfunction "17_SCL2_17_SCL2") (pintype "bidirectional"))
    )
    (net (code "54") (name "unconnected-(U$5-Pad18_RESERVED)") (class "Default")
      (node (ref "U$5") (pin "18_RESERVED") (pinfunction "18_RESERVED_18_RESERVED") (pintype "bidirectional"))
    )
    (net (code "55") (name "unconnected-(U1-ADC6-Pad19)") (class "Default")
      (node (ref "U1") (pin "19") (pinfunction "ADC6_19") (pintype "input"))
    )
    (net (code "56") (name "unconnected-(U1-ADC7-Pad22)") (class "Default")
      (node (ref "U1") (pin "22") (pinfunction "ADC7_22") (pintype "input"))
    )
    (net (code "57") (name "unconnected-(U1-PC1-Pad24)") (class "Default")
      (node (ref "U1") (pin "24") (pinfunction "PC1_24") (pintype "bidirectional"))
    )
    (net (code "58") (name "unconnected-(U1-PC2-Pad25)") (class "Default")
      (node (ref "U1") (pin "25") (pinfunction "PC2_25") (pintype "bidirectional"))
    )
    (net (code "59") (name "unconnected-(U1-PC3-Pad26)") (class "Default")
      (node (ref "U1") (pin "26") (pinfunction "PC3_26") (pintype "bidirectional"))
    )
    (net (code "60") (name "unconnected-(U1-PC4-Pad27)") (class "Default")
      (node (ref "U1") (pin "27") (pinfunction "PC4_27") (pintype "bidirectional"))
    )
    (net (code "61") (name "unconnected-(U1-PC5-Pad28)") (class "Default")
      (node (ref "U1") (pin "28") (pinfunction "PC5_28") (pintype "bidirectional"))
    )
    (net (code "62") (name "unconnected-(U1-PD5-Pad9)") (class "Default")
      (node (ref "U1") (pin "9") (pinfunction "PD5_9") (pintype "bidirectional"))
    )
    (net (code "63") (name "unconnected-(U1-PD6-Pad10)") (class "Default")
      (node (ref "U1") (pin "10") (pinfunction "PD6_10") (pintype "bidirectional"))
    )
  )
)
